# RGMII_SDIO_I2S.net
KiCad netlist of a schematic drawn in Altium Designer
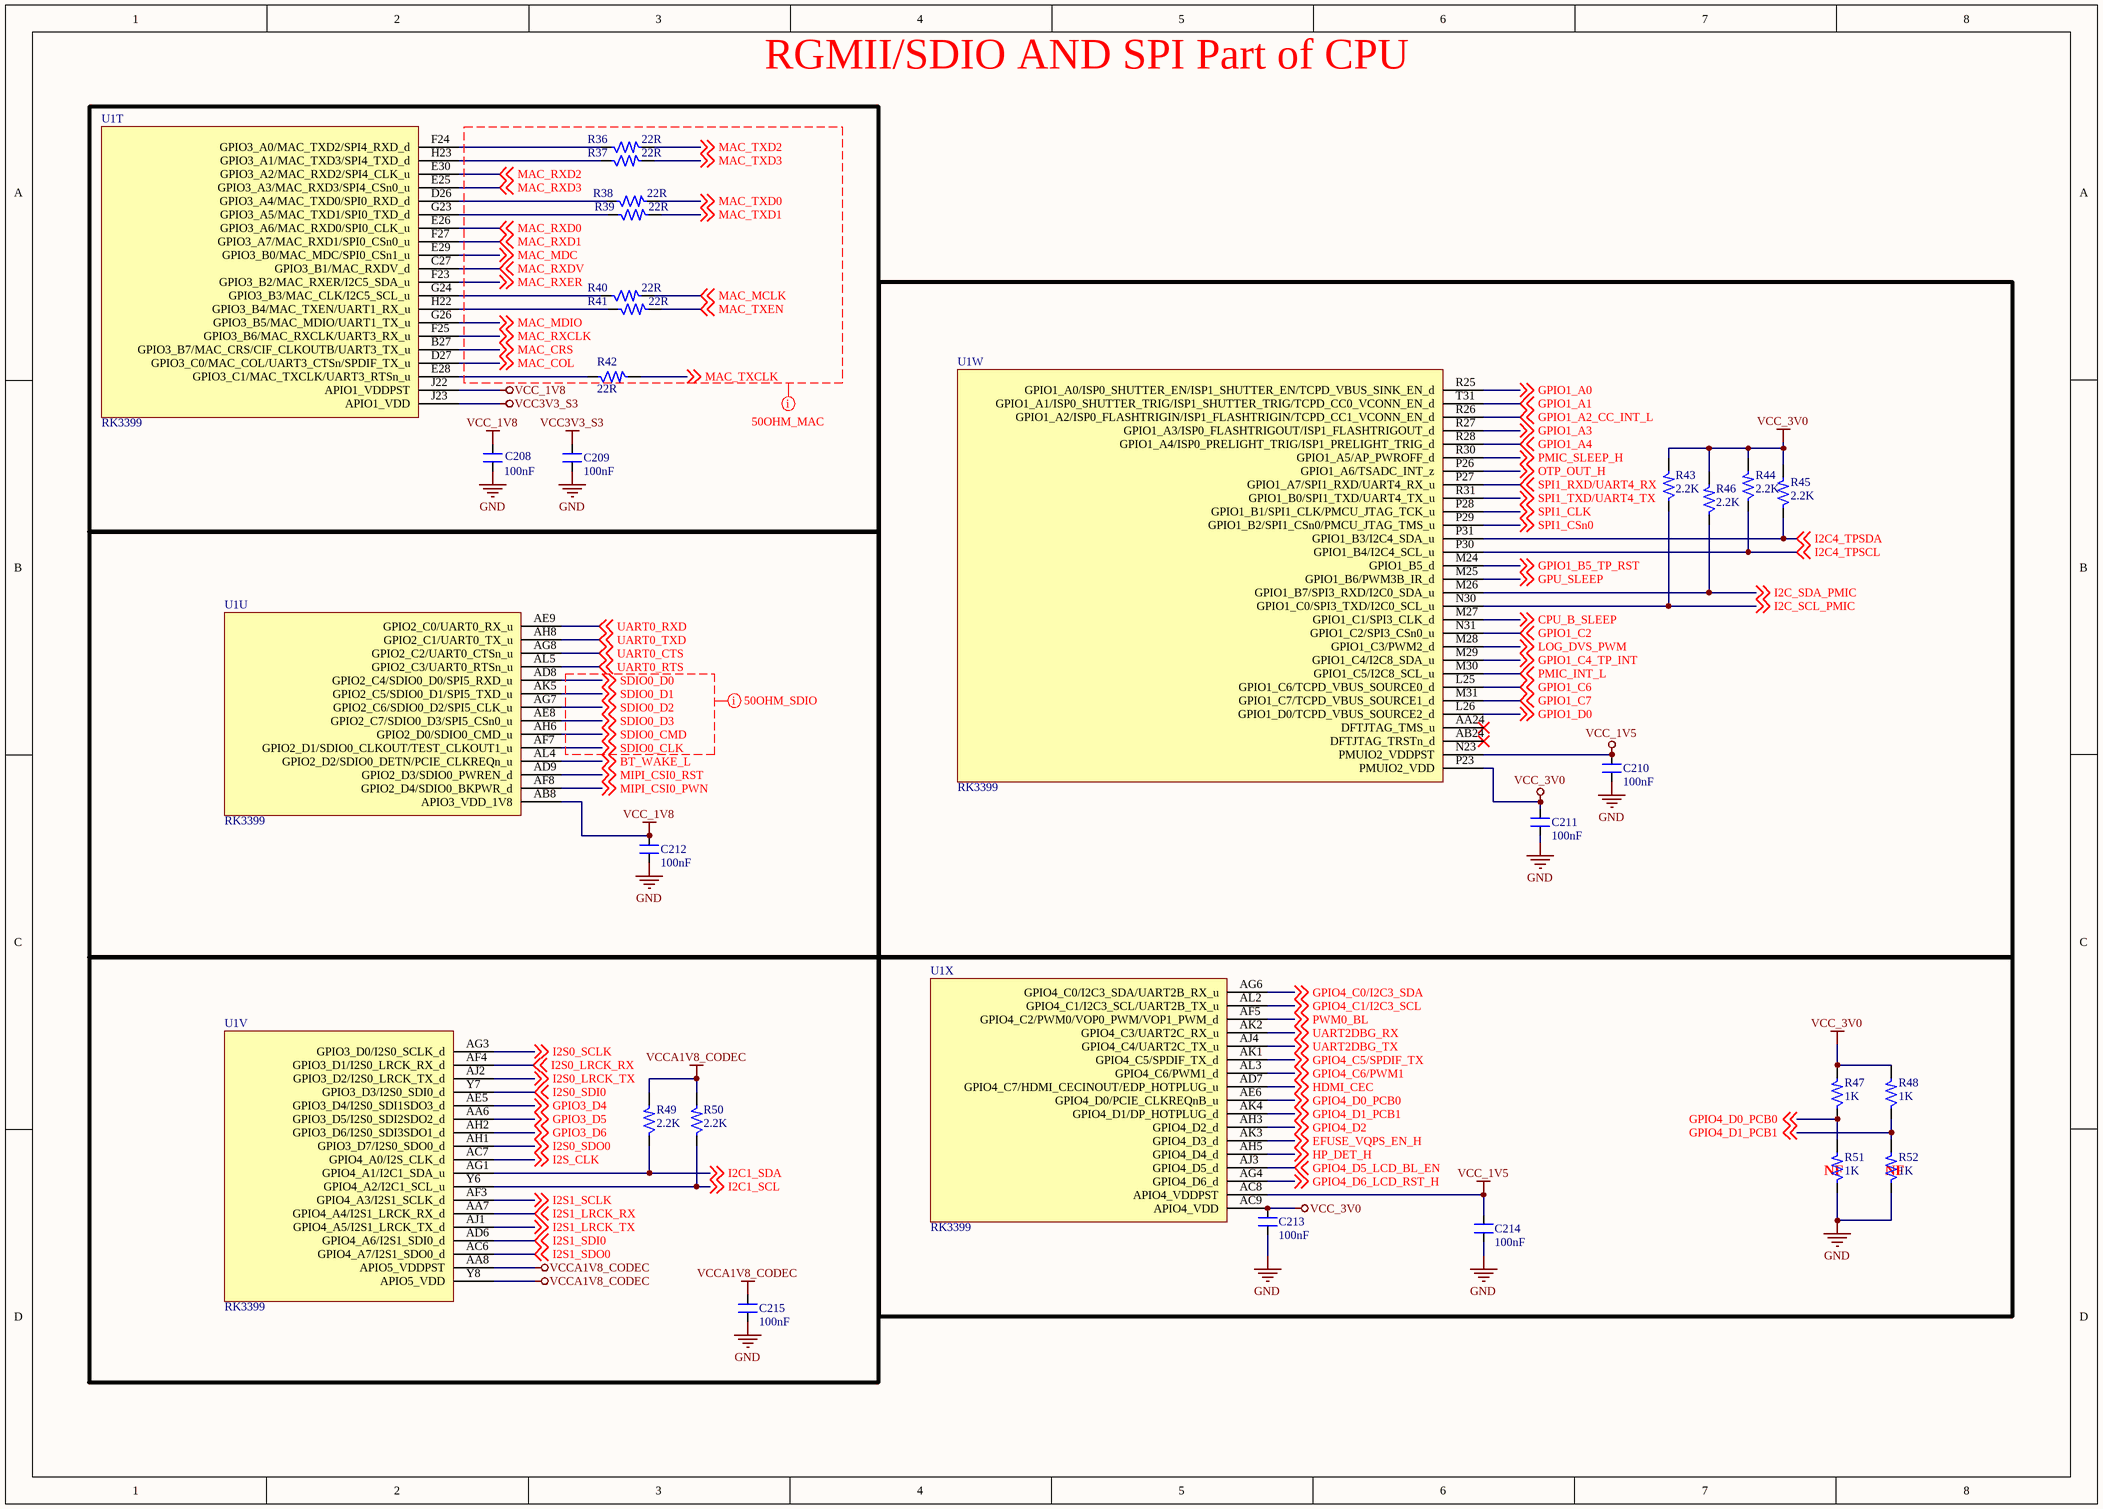
[diagram p0: RGMII_SDIO_I2S.SchDoc]

(export (version "E")
  (design (tool "Eeschema 10.0.6"))
  (components
    (comp (ref "C208")
      (value "100nF")
      (footprint "CAP_0201")
      (description "0.1µF ±10% 25V Ceramic Capacitor X5R 0201 (0603 Metric)")
      (fields
        (field (name "MANUFACTURER") "TDK Corporation")
        (field (name "MANUFACTURER PART NUMBER") "C0603X5R1E104K030BB")
      )
      (libsource (lib "RK3399 _Module_Intlib") (part "CAP_100nF-25V-10%-0201"))
    )
    (comp (ref "C209")
      (value "100nF")
      (footprint "CAP_0201")
      (description "0.1µF ±10% 25V Ceramic Capacitor X5R 0201 (0603 Metric)")
      (fields
        (field (name "MANUFACTURER") "TDK Corporation")
        (field (name "MANUFACTURER PART NUMBER") "C0603X5R1E104K030BB")
      )
      (libsource (lib "RK3399 _Module_Intlib") (part "CAP_100nF-25V-10%-0201"))
    )
    (comp (ref "C210")
      (value "100nF")
      (footprint "CAP_0201")
      (description "0.1µF ±10% 25V Ceramic Capacitor X5R 0201 (0603 Metric)")
      (fields
        (field (name "MANUFACTURER") "TDK Corporation")
        (field (name "MANUFACTURER PART NUMBER") "C0603X5R1E104K030BB")
      )
      (libsource (lib "RK3399 _Module_Intlib") (part "CAP_100nF-25V-10%-0201"))
    )
    (comp (ref "C211")
      (value "100nF")
      (footprint "CAP_0201")
      (description "0.1µF ±10% 25V Ceramic Capacitor X5R 0201 (0603 Metric)")
      (fields
        (field (name "MANUFACTURER") "TDK Corporation")
        (field (name "MANUFACTURER PART NUMBER") "C0603X5R1E104K030BB")
      )
      (libsource (lib "RK3399 _Module_Intlib") (part "CAP_100nF-25V-10%-0201"))
    )
    (comp (ref "C212")
      (value "100nF")
      (footprint "CAP_0201")
      (description "0.1µF ±10% 25V Ceramic Capacitor X5R 0201 (0603 Metric)")
      (fields
        (field (name "MANUFACTURER") "TDK Corporation")
        (field (name "MANUFACTURER PART NUMBER") "C0603X5R1E104K030BB")
      )
      (libsource (lib "RK3399 _Module_Intlib") (part "CAP_100nF-25V-10%-0201"))
    )
    (comp (ref "C213")
      (value "100nF")
      (footprint "CAP_0201")
      (description "0.1µF ±10% 25V Ceramic Capacitor X5R 0201 (0603 Metric)")
      (fields
        (field (name "MANUFACTURER") "TDK Corporation")
        (field (name "MANUFACTURER PART NUMBER") "C0603X5R1E104K030BB")
      )
      (libsource (lib "RK3399 _Module_Intlib") (part "CAP_100nF-25V-10%-0201"))
    )
    (comp (ref "C214")
      (value "100nF")
      (footprint "CAP_0201")
      (description "0.1µF ±10% 25V Ceramic Capacitor X5R 0201 (0603 Metric)")
      (fields
        (field (name "MANUFACTURER") "TDK Corporation")
        (field (name "MANUFACTURER PART NUMBER") "C0603X5R1E104K030BB")
      )
      (libsource (lib "RK3399 _Module_Intlib") (part "CAP_100nF-25V-10%-0201"))
    )
    (comp (ref "C215")
      (value "100nF")
      (footprint "CAP_0201")
      (description "0.1µF ±10% 25V Ceramic Capacitor X5R 0201 (0603 Metric)")
      (fields
        (field (name "MANUFACTURER") "TDK Corporation")
        (field (name "MANUFACTURER PART NUMBER") "C0603X5R1E104K030BB")
      )
      (libsource (lib "RK3399 _Module_Intlib") (part "CAP_100nF-25V-10%-0201"))
    )
    (comp (ref "R36")
      (value "22R")
      (footprint "RES_0201")
      (description "22 Ohms ±1% 0.05W, 1/20W Chip Resistor 0201 (0603 Metric) Moisture Resistant Thick Film")
      (fields
        (field (name "MANUFACTURER") "Yageo")
        (field (name "MANUFACTURER PART NUMBER") "RC0201FR-0722RL")
      )
      (libsource (lib "EsteemPCB_SOM_Course_intlib") (part "RES_22R-0.05W-1%-0201"))
    )
    (comp (ref "R37")
      (value "22R")
      (footprint "RES_0201")
      (description "22 Ohms ±1% 0.05W, 1/20W Chip Resistor 0201 (0603 Metric) Moisture Resistant Thick Film")
      (fields
        (field (name "MANUFACTURER") "Yageo")
        (field (name "MANUFACTURER PART NUMBER") "RC0201FR-0722RL")
      )
      (libsource (lib "EsteemPCB_SOM_Course_intlib") (part "RES_22R-0.05W-1%-0201"))
    )
    (comp (ref "R38")
      (value "22R")
      (footprint "RES_0201")
      (description "22 Ohms ±1% 0.05W, 1/20W Chip Resistor 0201 (0603 Metric) Moisture Resistant Thick Film")
      (fields
        (field (name "MANUFACTURER") "Yageo")
        (field (name "MANUFACTURER PART NUMBER") "RC0201FR-0722RL")
      )
      (libsource (lib "EsteemPCB_SOM_Course_intlib") (part "RES_22R-0.05W-1%-0201"))
    )
    (comp (ref "R39")
      (value "22R")
      (footprint "RES_0201")
      (description "22 Ohms ±1% 0.05W, 1/20W Chip Resistor 0201 (0603 Metric) Moisture Resistant Thick Film")
      (fields
        (field (name "MANUFACTURER") "Yageo")
        (field (name "MANUFACTURER PART NUMBER") "RC0201FR-0722RL")
      )
      (libsource (lib "EsteemPCB_SOM_Course_intlib") (part "RES_22R-0.05W-1%-0201"))
    )
    (comp (ref "R40")
      (value "22R")
      (footprint "RES_0201")
      (description "22 Ohms ±1% 0.05W, 1/20W Chip Resistor 0201 (0603 Metric) Moisture Resistant Thick Film")
      (fields
        (field (name "MANUFACTURER") "Yageo")
        (field (name "MANUFACTURER PART NUMBER") "RC0201FR-0722RL")
      )
      (libsource (lib "EsteemPCB_SOM_Course_intlib") (part "RES_22R-0.05W-1%-0201"))
    )
    (comp (ref "R41")
      (value "22R")
      (footprint "RES_0201")
      (description "22 Ohms ±1% 0.05W, 1/20W Chip Resistor 0201 (0603 Metric) Moisture Resistant Thick Film")
      (fields
        (field (name "MANUFACTURER") "Yageo")
        (field (name "MANUFACTURER PART NUMBER") "RC0201FR-0722RL")
      )
      (libsource (lib "EsteemPCB_SOM_Course_intlib") (part "RES_22R-0.05W-1%-0201"))
    )
    (comp (ref "R42")
      (value "22R")
      (footprint "RES_0201")
      (description "22 Ohms ±1% 0.05W, 1/20W Chip Resistor 0201 (0603 Metric) Moisture Resistant Thick Film")
      (fields
        (field (name "MANUFACTURER") "Yageo")
        (field (name "MANUFACTURER PART NUMBER") "RC0201FR-0722RL")
      )
      (libsource (lib "EsteemPCB_SOM_Course_intlib") (part "RES_22R-0.05W-1%-0201"))
    )
    (comp (ref "R43")
      (value "2.2K")
      (footprint "RES_0201")
      (description "2.2 kOhms ±1% 0.05W, 1/20W Chip Resistor 0201 (0603 Metric) Thick Film")
      (fields
        (field (name "MANUFACTURER") "Stackpole Electronics Inc")
        (field (name "MANUFACTURER PART NUMBER") "RMCF0201FT2K20")
      )
      (libsource (lib "RK3399 _Module_Intlib") (part "RES_2.2K-0.05W-1%-0201"))
    )
    (comp (ref "R44")
      (value "2.2K")
      (footprint "RES_0201")
      (description "2.2 kOhms ±1% 0.05W, 1/20W Chip Resistor 0201 (0603 Metric) Thick Film")
      (fields
        (field (name "MANUFACTURER") "Stackpole Electronics Inc")
        (field (name "MANUFACTURER PART NUMBER") "RMCF0201FT2K20")
      )
      (libsource (lib "RK3399 _Module_Intlib") (part "RES_2.2K-0.05W-1%-0201"))
    )
    (comp (ref "R45")
      (value "2.2K")
      (footprint "RES_0201")
      (description "2.2 kOhms ±1% 0.05W, 1/20W Chip Resistor 0201 (0603 Metric) Thick Film")
      (fields
        (field (name "MANUFACTURER") "Stackpole Electronics Inc")
        (field (name "MANUFACTURER PART NUMBER") "RMCF0201FT2K20")
      )
      (libsource (lib "RK3399 _Module_Intlib") (part "RES_2.2K-0.05W-1%-0201"))
    )
    (comp (ref "R46")
      (value "2.2K")
      (footprint "RES_0201")
      (description "2.2 kOhms ±1% 0.05W, 1/20W Chip Resistor 0201 (0603 Metric) Thick Film")
      (fields
        (field (name "MANUFACTURER") "Stackpole Electronics Inc")
        (field (name "MANUFACTURER PART NUMBER") "RMCF0201FT2K20")
      )
      (libsource (lib "RK3399 _Module_Intlib") (part "RES_2.2K-0.05W-1%-0201"))
    )
    (comp (ref "R47")
      (value "1K")
      (footprint "RES_0201")
      (description "1 kOhms ±1% 0.05W, 1/20W Chip Resistor 0201 (0603 Metric) Thick Film")
      (fields
        (field (name "MANUFACTURER") "Yageo")
        (field (name "MANUFACTURER PART NUMBER") "RC0201FR-071KL")
      )
      (libsource (lib "RK3399 _Module_Intlib") (part "RES_1K-0.05W-1%-0201"))
    )
    (comp (ref "R48")
      (value "1K")
      (footprint "RES_0201")
      (description "1 kOhms ±1% 0.05W, 1/20W Chip Resistor 0201 (0603 Metric) Thick Film")
      (fields
        (field (name "MANUFACTURER") "Yageo")
        (field (name "MANUFACTURER PART NUMBER") "RC0201FR-071KL")
      )
      (libsource (lib "RK3399 _Module_Intlib") (part "RES_1K-0.05W-1%-0201"))
    )
    (comp (ref "R49")
      (value "2.2K")
      (footprint "RES_0201")
      (description "2.2 kOhms ±1% 0.05W, 1/20W Chip Resistor 0201 (0603 Metric) Thick Film")
      (fields
        (field (name "MANUFACTURER") "Stackpole Electronics Inc")
        (field (name "MANUFACTURER PART NUMBER") "RMCF0201FT2K20")
      )
      (libsource (lib "RK3399 _Module_Intlib") (part "RES_2.2K-0.05W-1%-0201"))
    )
    (comp (ref "R50")
      (value "2.2K")
      (footprint "RES_0201")
      (description "2.2 kOhms ±1% 0.05W, 1/20W Chip Resistor 0201 (0603 Metric) Thick Film")
      (fields
        (field (name "MANUFACTURER") "Stackpole Electronics Inc")
        (field (name "MANUFACTURER PART NUMBER") "RMCF0201FT2K20")
      )
      (libsource (lib "RK3399 _Module_Intlib") (part "RES_2.2K-0.05W-1%-0201"))
    )
    (comp (ref "R51")
      (value "1K")
      (footprint "RES_0201")
      (description "1 kOhms ±1% 0.05W, 1/20W Chip Resistor 0201 (0603 Metric) Thick Film")
      (fields
        (field (name "MANUFACTURER") "Yageo")
        (field (name "MANUFACTURER PART NUMBER") "RC0201FR-071KL")
      )
      (libsource (lib "RK3399 _Module_Intlib") (part "RES_1K-0.05W-1%-0201"))
    )
    (comp (ref "R52")
      (value "1K")
      (footprint "RES_0201")
      (description "1 kOhms ±1% 0.05W, 1/20W Chip Resistor 0201 (0603 Metric) Thick Film")
      (fields
        (field (name "MANUFACTURER") "Yageo")
        (field (name "MANUFACTURER PART NUMBER") "RC0201FR-071KL")
      )
      (libsource (lib "RK3399 _Module_Intlib") (part "RES_1K-0.05W-1%-0201"))
    )
    (comp (ref "U1")
      (value "RK3399")
      (footprint "FBGA828_23_826X826")
      (description "RK3399 is a low power, high performance processor for computing, personal mobile.")
      (fields (field (name "MANUFACTURER") "Rockchip"))
      (libsource (lib "RK3399 _Module_Schlib") (part "IC_RK3399-FCBGA828"))
    )
  )
  (nets
    (net (code "1") (name "BT_WAKE_L") (class "Default")
      (node (ref "U1") (pin "AL4") (pinfunction "GPIO2_D2/SDIO0_DETN/PCIE_CLKREQn_u_AL4") (pintype "passive"))
    )
    (net (code "2") (name "CPU_B_SLEEP") (class "Default")
      (node (ref "U1") (pin "M27") (pinfunction "GPIO1_C1/SPI3_CLK_d_M27") (pintype "passive"))
    )
    (net (code "3") (name "EFUSE_VQPS_EN_H") (class "Default")
      (node (ref "U1") (pin "AK3") (pinfunction "GPIO4_D3_d_AK3") (pintype "passive"))
    )
    (net (code "4") (name "GND") (class "Default")
      (node (ref "C208") (pin "1") (pinfunction "1_1") (pintype "passive"))
      (node (ref "C209") (pin "1") (pinfunction "1_1") (pintype "passive"))
      (node (ref "C210") (pin "1") (pinfunction "1_1") (pintype "passive"))
      (node (ref "C211") (pin "1") (pinfunction "1_1") (pintype "passive"))
      (node (ref "C212") (pin "1") (pinfunction "1_1") (pintype "passive"))
      (node (ref "C213") (pin "1") (pinfunction "1_1") (pintype "passive"))
      (node (ref "C214") (pin "1") (pinfunction "1_1") (pintype "passive"))
      (node (ref "C215") (pin "1") (pinfunction "1_1") (pintype "passive"))
      (node (ref "R51") (pin "1") (pinfunction "1_1") (pintype "passive"))
      (node (ref "R52") (pin "1") (pinfunction "1_1") (pintype "passive"))
    )
    (net (code "5") (name "GPIO1_A0") (class "Default")
      (node (ref "U1") (pin "R25") (pinfunction "GPIO1_A0/ISP0_SHUTTER_EN/ISP1_SHUTTER_EN/TCPD_VBUS_SINK_EN_d_R25") (pintype "passive"))
    )
    (net (code "6") (name "GPIO1_A1") (class "Default")
      (node (ref "U1") (pin "T31") (pinfunction "GPIO1_A1/ISP0_SHUTTER_TRIG/ISP1_SHUTTER_TRIG/TCPD_CC0_VCONN_EN_d_T31") (pintype "passive"))
    )
    (net (code "7") (name "GPIO1_A2_CC_INT_L") (class "Default")
      (node (ref "U1") (pin "R26") (pinfunction "GPIO1_A2/ISP0_FLASHTRIGIN/ISP1_FLASHTRIGIN/TCPD_CC1_VCONN_EN_d_R26") (pintype "passive"))
    )
    (net (code "8") (name "GPIO1_A3") (class "Default")
      (node (ref "U1") (pin "R27") (pinfunction "GPIO1_A3/ISP0_FLASHTRIGOUT/ISP1_FLASHTRIGOUT_d_R27") (pintype "passive"))
    )
    (net (code "9") (name "GPIO1_A4") (class "Default")
      (node (ref "U1") (pin "R28") (pinfunction "GPIO1_A4/ISP0_PRELIGHT_TRIG/ISP1_PRELIGHT_TRIG_d_R28") (pintype "passive"))
    )
    (net (code "10") (name "GPIO1_B5_TP_RST") (class "Default")
      (node (ref "U1") (pin "M24") (pinfunction "GPIO1_B5_d_M24") (pintype "passive"))
    )
    (net (code "11") (name "GPIO1_C2") (class "Default")
      (node (ref "U1") (pin "N31") (pinfunction "GPIO1_C2/SPI3_CSn0_u_N31") (pintype "passive"))
    )
    (net (code "12") (name "GPIO1_C4_TP_INT") (class "Default")
      (node (ref "U1") (pin "M29") (pinfunction "GPIO1_C4/I2C8_SDA_u_M29") (pintype "passive"))
    )
    (net (code "13") (name "GPIO1_C6") (class "Default")
      (node (ref "U1") (pin "L25") (pinfunction "GPIO1_C6/TCPD_VBUS_SOURCE0_d_L25") (pintype "passive"))
    )
    (net (code "14") (name "GPIO1_C7") (class "Default")
      (node (ref "U1") (pin "M31") (pinfunction "GPIO1_C7/TCPD_VBUS_SOURCE1_d_M31") (pintype "passive"))
    )
    (net (code "15") (name "GPIO1_D0") (class "Default")
      (node (ref "U1") (pin "L26") (pinfunction "GPIO1_D0/TCPD_VBUS_SOURCE2_d_L26") (pintype "passive"))
    )
    (net (code "16") (name "GPIO3_D4") (class "Default")
      (node (ref "U1") (pin "AE5") (pinfunction "GPIO3_D4/I2S0_SDI1SDO3_d_AE5") (pintype "passive"))
    )
    (net (code "17") (name "GPIO3_D5") (class "Default")
      (node (ref "U1") (pin "AA6") (pinfunction "GPIO3_D5/I2S0_SDI2SDO2_d_AA6") (pintype "passive"))
    )
    (net (code "18") (name "GPIO3_D6") (class "Default")
      (node (ref "U1") (pin "AH2") (pinfunction "GPIO3_D6/I2S0_SDI3SDO1_d_AH2") (pintype "passive"))
    )
    (net (code "19") (name "GPIO4_C0{slash}I2C3_SDA") (class "Default")
      (node (ref "U1") (pin "AG6") (pinfunction "GPIO4_C0/I2C3_SDA/UART2B_RX_u_AG6") (pintype "passive"))
    )
    (net (code "20") (name "GPIO4_C1{slash}I2C3_SCL") (class "Default")
      (node (ref "U1") (pin "AL2") (pinfunction "GPIO4_C1/I2C3_SCL/UART2B_TX_u_AL2") (pintype "passive"))
    )
    (net (code "21") (name "GPIO4_C5{slash}SPDIF_TX") (class "Default")
      (node (ref "U1") (pin "AK1") (pinfunction "GPIO4_C5/SPDIF_TX_d_AK1") (pintype "passive"))
    )
    (net (code "22") (name "GPIO4_C6{slash}PWM1") (class "Default")
      (node (ref "U1") (pin "AL3") (pinfunction "GPIO4_C6/PWM1_d_AL3") (pintype "passive"))
    )
    (net (code "23") (name "GPIO4_D0_PCB0") (class "Default")
      (node (ref "R47") (pin "1") (pinfunction "1_1") (pintype "passive"))
      (node (ref "R51") (pin "2") (pinfunction "2_2") (pintype "passive"))
      (node (ref "U1") (pin "AE6") (pinfunction "GPIO4_D0/PCIE_CLKREQnB_u_AE6") (pintype "passive"))
    )
    (net (code "24") (name "GPIO4_D1_PCB1") (class "Default")
      (node (ref "R48") (pin "1") (pinfunction "1_1") (pintype "passive"))
      (node (ref "R52") (pin "2") (pinfunction "2_2") (pintype "passive"))
      (node (ref "U1") (pin "AK4") (pinfunction "GPIO4_D1/DP_HOTPLUG_d_AK4") (pintype "passive"))
    )
    (net (code "25") (name "GPIO4_D2") (class "Default")
      (node (ref "U1") (pin "AH3") (pinfunction "GPIO4_D2_d_AH3") (pintype "passive"))
    )
    (net (code "26") (name "GPIO4_D5_LCD_BL_EN") (class "Default")
      (node (ref "U1") (pin "AJ3") (pinfunction "GPIO4_D5_d_AJ3") (pintype "passive"))
    )
    (net (code "27") (name "GPIO4_D6_LCD_RST_H") (class "Default")
      (node (ref "U1") (pin "AG4") (pinfunction "GPIO4_D6_d_AG4") (pintype "passive"))
    )
    (net (code "28") (name "GPU_SLEEP") (class "Default")
      (node (ref "U1") (pin "M25") (pinfunction "GPIO1_B6/PWM3B_IR_d_M25") (pintype "passive"))
    )
    (net (code "29") (name "HDMI_CEC") (class "Default")
      (node (ref "U1") (pin "AD7") (pinfunction "GPIO4_C7/HDMI_CECINOUT/EDP_HOTPLUG_u_AD7") (pintype "passive"))
    )
    (net (code "30") (name "HP_DET_H") (class "Default")
      (node (ref "U1") (pin "AH5") (pinfunction "GPIO4_D4_d_AH5") (pintype "passive"))
    )
    (net (code "31") (name "I2C1_SCL") (class "Default")
      (node (ref "R50") (pin "1") (pinfunction "1_1") (pintype "passive"))
      (node (ref "U1") (pin "Y6") (pinfunction "GPIO4_A2/I2C1_SCL_u_Y6") (pintype "passive"))
    )
    (net (code "32") (name "I2C1_SDA") (class "Default")
      (node (ref "R49") (pin "1") (pinfunction "1_1") (pintype "passive"))
      (node (ref "U1") (pin "AG1") (pinfunction "GPIO4_A1/I2C1_SDA_u_AG1") (pintype "passive"))
    )
    (net (code "33") (name "I2C4_TPSCL") (class "Default")
      (node (ref "R44") (pin "1") (pinfunction "1_1") (pintype "passive"))
      (node (ref "U1") (pin "P30") (pinfunction "GPIO1_B4/I2C4_SCL_u_P30") (pintype "passive"))
    )
    (net (code "34") (name "I2C4_TPSDA") (class "Default")
      (node (ref "R45") (pin "1") (pinfunction "1_1") (pintype "passive"))
      (node (ref "U1") (pin "P31") (pinfunction "GPIO1_B3/I2C4_SDA_u_P31") (pintype "passive"))
    )
    (net (code "35") (name "I2C_SCL_PMIC") (class "Default")
      (node (ref "R43") (pin "1") (pinfunction "1_1") (pintype "passive"))
      (node (ref "U1") (pin "N30") (pinfunction "GPIO1_C0/SPI3_TXD/I2C0_SCL_u_N30") (pintype "passive"))
    )
    (net (code "36") (name "I2C_SDA_PMIC") (class "Default")
      (node (ref "R46") (pin "1") (pinfunction "1_1") (pintype "passive"))
      (node (ref "U1") (pin "M26") (pinfunction "GPIO1_B7/SPI3_RXD/I2C0_SDA_u_M26") (pintype "passive"))
    )
    (net (code "37") (name "I2S0_LRCK_RX") (class "Default")
      (node (ref "U1") (pin "AF4") (pinfunction "GPIO3_D1/I2S0_LRCK_RX_d_AF4") (pintype "passive"))
    )
    (net (code "38") (name "I2S0_LRCK_TX") (class "Default")
      (node (ref "U1") (pin "AJ2") (pinfunction "GPIO3_D2/I2S0_LRCK_TX_d_AJ2") (pintype "passive"))
    )
    (net (code "39") (name "I2S0_SCLK") (class "Default")
      (node (ref "U1") (pin "AG3") (pinfunction "GPIO3_D0/I2S0_SCLK_d_AG3") (pintype "passive"))
    )
    (net (code "40") (name "I2S0_SDI0") (class "Default")
      (node (ref "U1") (pin "Y7") (pinfunction "GPIO3_D3/I2S0_SDI0_d_Y7") (pintype "passive"))
    )
    (net (code "41") (name "I2S0_SDO0") (class "Default")
      (node (ref "U1") (pin "AH1") (pinfunction "GPIO3_D7/I2S0_SDO0_d_AH1") (pintype "passive"))
    )
    (net (code "42") (name "I2S1_LRCK_RX") (class "Default")
      (node (ref "U1") (pin "AA7") (pinfunction "GPIO4_A4/I2S1_LRCK_RX_d_AA7") (pintype "passive"))
    )
    (net (code "43") (name "I2S1_LRCK_TX") (class "Default")
      (node (ref "U1") (pin "AJ1") (pinfunction "GPIO4_A5/I2S1_LRCK_TX_d_AJ1") (pintype "passive"))
    )
    (net (code "44") (name "I2S1_SCLK") (class "Default")
      (node (ref "U1") (pin "AF3") (pinfunction "GPIO4_A3/I2S1_SCLK_d_AF3") (pintype "passive"))
    )
    (net (code "45") (name "I2S1_SDI0") (class "Default")
      (node (ref "U1") (pin "AD6") (pinfunction "GPIO4_A6/I2S1_SDI0_d_AD6") (pintype "passive"))
    )
    (net (code "46") (name "I2S1_SDO0") (class "Default")
      (node (ref "U1") (pin "AC6") (pinfunction "GPIO4_A7/I2S1_SDO0_d_AC6") (pintype "passive"))
    )
    (net (code "47") (name "I2S_CLK") (class "Default")
      (node (ref "U1") (pin "AC7") (pinfunction "GPIO4_A0/I2S_CLK_d_AC7") (pintype "passive"))
    )
    (net (code "48") (name "LOG_DVS_PWM") (class "Default")
      (node (ref "U1") (pin "M28") (pinfunction "GPIO1_C3/PWM2_d_M28") (pintype "passive"))
    )
    (net (code "49") (name "MAC_COL") (class "Default")
      (node (ref "U1") (pin "D27") (pinfunction "GPIO3_C0/MAC_COL/UART3_CTSn/SPDIF_TX_u_D27") (pintype "passive"))
    )
    (net (code "50") (name "MAC_CRS") (class "Default")
      (node (ref "U1") (pin "B27") (pinfunction "GPIO3_B7/MAC_CRS/CIF_CLKOUTB/UART3_TX_u_B27") (pintype "passive"))
    )
    (net (code "51") (name "MAC_MCLK") (class "Default")
      (node (ref "R40") (pin "2") (pinfunction "2_2") (pintype "passive"))
    )
    (net (code "52") (name "MAC_MDC") (class "Default")
      (node (ref "U1") (pin "E29") (pinfunction "GPIO3_B0/MAC_MDC/SPI0_CSn1_u_E29") (pintype "passive"))
    )
    (net (code "53") (name "MAC_MDIO") (class "Default")
      (node (ref "U1") (pin "G26") (pinfunction "GPIO3_B5/MAC_MDIO/UART1_TX_u_G26") (pintype "passive"))
    )
    (net (code "54") (name "MAC_RXCLK") (class "Default")
      (node (ref "U1") (pin "F25") (pinfunction "GPIO3_B6/MAC_RXCLK/UART3_RX_u_F25") (pintype "passive"))
    )
    (net (code "55") (name "MAC_RXD0") (class "Default")
      (node (ref "U1") (pin "E26") (pinfunction "GPIO3_A6/MAC_RXD0/SPI0_CLK_u_E26") (pintype "passive"))
    )
    (net (code "56") (name "MAC_RXD1") (class "Default")
      (node (ref "U1") (pin "F27") (pinfunction "GPIO3_A7/MAC_RXD1/SPI0_CSn0_u_F27") (pintype "passive"))
    )
    (net (code "57") (name "MAC_RXD2") (class "Default")
      (node (ref "U1") (pin "E30") (pinfunction "GPIO3_A2/MAC_RXD2/SPI4_CLK_u_E30") (pintype "passive"))
    )
    (net (code "58") (name "MAC_RXD3") (class "Default")
      (node (ref "U1") (pin "E25") (pinfunction "GPIO3_A3/MAC_RXD3/SPI4_CSn0_u_E25") (pintype "passive"))
    )
    (net (code "59") (name "MAC_RXDV") (class "Default")
      (node (ref "U1") (pin "C27") (pinfunction "GPIO3_B1/MAC_RXDV_d_C27") (pintype "passive"))
    )
    (net (code "60") (name "MAC_RXER") (class "Default")
      (node (ref "U1") (pin "F23") (pinfunction "GPIO3_B2/MAC_RXER/I2C5_SDA_u_F23") (pintype "passive"))
    )
    (net (code "61") (name "MAC_TXCLK") (class "Default")
      (node (ref "R42") (pin "2") (pinfunction "2_2") (pintype "passive"))
    )
    (net (code "62") (name "MAC_TXD0") (class "Default")
      (node (ref "R38") (pin "2") (pinfunction "2_2") (pintype "passive"))
    )
    (net (code "63") (name "MAC_TXD1") (class "Default")
      (node (ref "R39") (pin "2") (pinfunction "2_2") (pintype "passive"))
    )
    (net (code "64") (name "MAC_TXD2") (class "Default")
      (node (ref "R36") (pin "2") (pinfunction "2_2") (pintype "passive"))
    )
    (net (code "65") (name "MAC_TXD3") (class "Default")
      (node (ref "R37") (pin "2") (pinfunction "2_2") (pintype "passive"))
    )
    (net (code "66") (name "MAC_TXEN") (class "Default")
      (node (ref "R41") (pin "2") (pinfunction "2_2") (pintype "passive"))
    )
    (net (code "67") (name "MIPI_CSI0_PWN") (class "Default")
      (node (ref "U1") (pin "AF8") (pinfunction "GPIO2_D4/SDIO0_BKPWR_d_AF8") (pintype "passive"))
    )
    (net (code "68") (name "MIPI_CSI0_RST") (class "Default")
      (node (ref "U1") (pin "AD9") (pinfunction "GPIO2_D3/SDIO0_PWREN_d_AD9") (pintype "passive"))
    )
    (net (code "69") (name "Net-(U1T-GPIO3_A0{slash}MAC_TXD2{slash}SPI4_RXD_d)") (class "Default")
      (node (ref "R36") (pin "1") (pinfunction "1_1") (pintype "passive"))
      (node (ref "U1") (pin "F24") (pinfunction "GPIO3_A0/MAC_TXD2/SPI4_RXD_d_F24") (pintype "passive"))
    )
    (net (code "70") (name "Net-(U1T-GPIO3_A1{slash}MAC_TXD3{slash}SPI4_TXD_d)") (class "Default")
      (node (ref "R37") (pin "1") (pinfunction "1_1") (pintype "passive"))
      (node (ref "U1") (pin "H23") (pinfunction "GPIO3_A1/MAC_TXD3/SPI4_TXD_d_H23") (pintype "passive"))
    )
    (net (code "71") (name "Net-(U1T-GPIO3_A4{slash}MAC_TXD0{slash}SPI0_RXD_d)") (class "Default")
      (node (ref "R38") (pin "1") (pinfunction "1_1") (pintype "passive"))
      (node (ref "U1") (pin "D26") (pinfunction "GPIO3_A4/MAC_TXD0/SPI0_RXD_d_D26") (pintype "passive"))
    )
    (net (code "72") (name "Net-(U1T-GPIO3_A5{slash}MAC_TXD1{slash}SPI0_TXD_d)") (class "Default")
      (node (ref "R39") (pin "1") (pinfunction "1_1") (pintype "passive"))
      (node (ref "U1") (pin "G23") (pinfunction "GPIO3_A5/MAC_TXD1/SPI0_TXD_d_G23") (pintype "passive"))
    )
    (net (code "73") (name "Net-(U1T-GPIO3_B3{slash}MAC_CLK{slash}I2C5_SCL_u)") (class "Default")
      (node (ref "R40") (pin "1") (pinfunction "1_1") (pintype "passive"))
      (node (ref "U1") (pin "G24") (pinfunction "GPIO3_B3/MAC_CLK/I2C5_SCL_u_G24") (pintype "passive"))
    )
    (net (code "74") (name "Net-(U1T-GPIO3_B4{slash}MAC_TXEN{slash}UART1_RX_u)") (class "Default")
      (node (ref "R41") (pin "1") (pinfunction "1_1") (pintype "passive"))
      (node (ref "U1") (pin "H22") (pinfunction "GPIO3_B4/MAC_TXEN/UART1_RX_u_H22") (pintype "passive"))
    )
    (net (code "75") (name "Net-(U1T-GPIO3_C1{slash}MAC_TXCLK{slash}UART3_RTSn_u)") (class "Default")
      (node (ref "R42") (pin "1") (pinfunction "1_1") (pintype "passive"))
      (node (ref "U1") (pin "E28") (pinfunction "GPIO3_C1/MAC_TXCLK/UART3_RTSn_u_E28") (pintype "passive"))
    )
    (net (code "76") (name "OTP_OUT_H") (class "Default")
      (node (ref "U1") (pin "P26") (pinfunction "GPIO1_A6/TSADC_INT_z_P26") (pintype "passive"))
    )
    (net (code "77") (name "PMIC_INT_L") (class "Default")
      (node (ref "U1") (pin "M30") (pinfunction "GPIO1_C5/I2C8_SCL_u_M30") (pintype "passive"))
    )
    (net (code "78") (name "PMIC_SLEEP_H") (class "Default")
      (node (ref "U1") (pin "R30") (pinfunction "GPIO1_A5/AP_PWROFF_d_R30") (pintype "passive"))
    )
    (net (code "79") (name "PWM0_BL") (class "Default")
      (node (ref "U1") (pin "AF5") (pinfunction "GPIO4_C2/PWM0/VOP0_PWM/VOP1_PWM_d_AF5") (pintype "passive"))
    )
    (net (code "80") (name "SDIO0_CLK") (class "Default")
      (node (ref "U1") (pin "AF7") (pinfunction "GPIO2_D1/SDIO0_CLKOUT/TEST_CLKOUT1_u_AF7") (pintype "passive"))
    )
    (net (code "81") (name "SDIO0_CMD") (class "Default")
      (node (ref "U1") (pin "AH6") (pinfunction "GPIO2_D0/SDIO0_CMD_u_AH6") (pintype "passive"))
    )
    (net (code "82") (name "SDIO0_D0") (class "Default")
      (node (ref "U1") (pin "AD8") (pinfunction "GPIO2_C4/SDIO0_D0/SPI5_RXD_u_AD8") (pintype "passive"))
    )
    (net (code "83") (name "SDIO0_D1") (class "Default")
      (node (ref "U1") (pin "AK5") (pinfunction "GPIO2_C5/SDIO0_D1/SPI5_TXD_u_AK5") (pintype "passive"))
    )
    (net (code "84") (name "SDIO0_D2") (class "Default")
      (node (ref "U1") (pin "AG7") (pinfunction "GPIO2_C6/SDIO0_D2/SPI5_CLK_u_AG7") (pintype "passive"))
    )
    (net (code "85") (name "SDIO0_D3") (class "Default")
      (node (ref "U1") (pin "AE8") (pinfunction "GPIO2_C7/SDIO0_D3/SPI5_CSn0_u_AE8") (pintype "passive"))
    )
    (net (code "86") (name "SPI1_CLK") (class "Default")
      (node (ref "U1") (pin "P28") (pinfunction "GPIO1_B1/SPI1_CLK/PMCU_JTAG_TCK_u_P28") (pintype "passive"))
    )
    (net (code "87") (name "SPI1_CSn0") (class "Default")
      (node (ref "U1") (pin "P29") (pinfunction "GPIO1_B2/SPI1_CSn0/PMCU_JTAG_TMS_u_P29") (pintype "passive"))
    )
    (net (code "88") (name "SPI1_RXD{slash}UART4_RX") (class "Default")
      (node (ref "U1") (pin "P27") (pinfunction "GPIO1_A7/SPI1_RXD/UART4_RX_u_P27") (pintype "passive"))
    )
    (net (code "89") (name "SPI1_TXD{slash}UART4_TX") (class "Default")
      (node (ref "U1") (pin "R31") (pinfunction "GPIO1_B0/SPI1_TXD/UART4_TX_u_R31") (pintype "passive"))
    )
    (net (code "90") (name "UART0_CTS") (class "Default")
      (node (ref "U1") (pin "AG8") (pinfunction "GPIO2_C2/UART0_CTSn_u_AG8") (pintype "passive"))
    )
    (net (code "91") (name "UART0_RTS") (class "Default")
      (node (ref "U1") (pin "AL5") (pinfunction "GPIO2_C3/UART0_RTSn_u_AL5") (pintype "passive"))
    )
    (net (code "92") (name "UART0_RXD") (class "Default")
      (node (ref "U1") (pin "AE9") (pinfunction "GPIO2_C0/UART0_RX_u_AE9") (pintype "passive"))
    )
    (net (code "93") (name "UART0_TXD") (class "Default")
      (node (ref "U1") (pin "AH8") (pinfunction "GPIO2_C1/UART0_TX_u_AH8") (pintype "passive"))
    )
    (net (code "94") (name "UART2DBG_RX") (class "Default")
      (node (ref "U1") (pin "AK2") (pinfunction "GPIO4_C3/UART2C_RX_u_AK2") (pintype "passive"))
    )
    (net (code "95") (name "UART2DBG_TX") (class "Default")
      (node (ref "U1") (pin "AJ4") (pinfunction "GPIO4_C4/UART2C_TX_u_AJ4") (pintype "passive"))
    )
    (net (code "96") (name "VCC3V3_S3") (class "Default")
      (node (ref "C209") (pin "2") (pinfunction "2_2") (pintype "passive"))
      (node (ref "U1") (pin "J23") (pinfunction "APIO1_VDD_J23") (pintype "passive"))
    )
    (net (code "97") (name "VCCA1V8_CODEC") (class "Default")
      (node (ref "C215") (pin "2") (pinfunction "2_2") (pintype "passive"))
      (node (ref "R49") (pin "2") (pinfunction "2_2") (pintype "passive"))
      (node (ref "R50") (pin "2") (pinfunction "2_2") (pintype "passive"))
      (node (ref "U1") (pin "AA8") (pinfunction "APIO5_VDDPST_AA8") (pintype "passive"))
      (node (ref "U1") (pin "Y8") (pinfunction "APIO5_VDD_Y8") (pintype "passive"))
    )
    (net (code "98") (name "VCC_1V5") (class "Default")
      (node (ref "C210") (pin "2") (pinfunction "2_2") (pintype "passive"))
      (node (ref "C214") (pin "2") (pinfunction "2_2") (pintype "passive"))
      (node (ref "U1") (pin "AC8") (pinfunction "APIO4_VDDPST_AC8") (pintype "passive"))
      (node (ref "U1") (pin "N23") (pinfunction "PMUIO2_VDDPST_N23") (pintype "passive"))
    )
    (net (code "99") (name "VCC_1V8") (class "Default")
      (node (ref "C208") (pin "2") (pinfunction "2_2") (pintype "passive"))
      (node (ref "C212") (pin "2") (pinfunction "2_2") (pintype "passive"))
      (node (ref "U1") (pin "AB8") (pinfunction "APIO3_VDD_1V8_AB8") (pintype "passive"))
      (node (ref "U1") (pin "J22") (pinfunction "APIO1_VDDPST_J22") (pintype "passive"))
    )
    (net (code "100") (name "VCC_3V0") (class "Default")
      (node (ref "C211") (pin "2") (pinfunction "2_2") (pintype "passive"))
      (node (ref "C213") (pin "2") (pinfunction "2_2") (pintype "passive"))
      (node (ref "R43") (pin "2") (pinfunction "2_2") (pintype "passive"))
      (node (ref "R44") (pin "2") (pinfunction "2_2") (pintype "passive"))
      (node (ref "R45") (pin "2") (pinfunction "2_2") (pintype "passive"))
      (node (ref "R46") (pin "2") (pinfunction "2_2") (pintype "passive"))
      (node (ref "R47") (pin "2") (pinfunction "2_2") (pintype "passive"))
      (node (ref "R48") (pin "2") (pinfunction "2_2") (pintype "passive"))
      (node (ref "U1") (pin "AC9") (pinfunction "APIO4_VDD_AC9") (pintype "passive"))
      (node (ref "U1") (pin "P23") (pinfunction "PMUIO2_VDD_P23") (pintype "passive"))
    )
    (net (code "101") (name "unconnected-(U1W-DFTJTAG_TMS_u-PadAA24)") (class "Default")
      (node (ref "U1") (pin "AA24") (pinfunction "DFTJTAG_TMS_u_AA24") (pintype "passive+no_connect"))
    )
    (net (code "102") (name "unconnected-(U1W-DFTJTAG_TRSTn_d-PadAB24)") (class "Default")
      (node (ref "U1") (pin "AB24") (pinfunction "DFTJTAG_TRSTn_d_AB24") (pintype "passive+no_connect"))
    )
  )
)
